# main.net
KiCad netlist of a schematic drawn in EAGLE
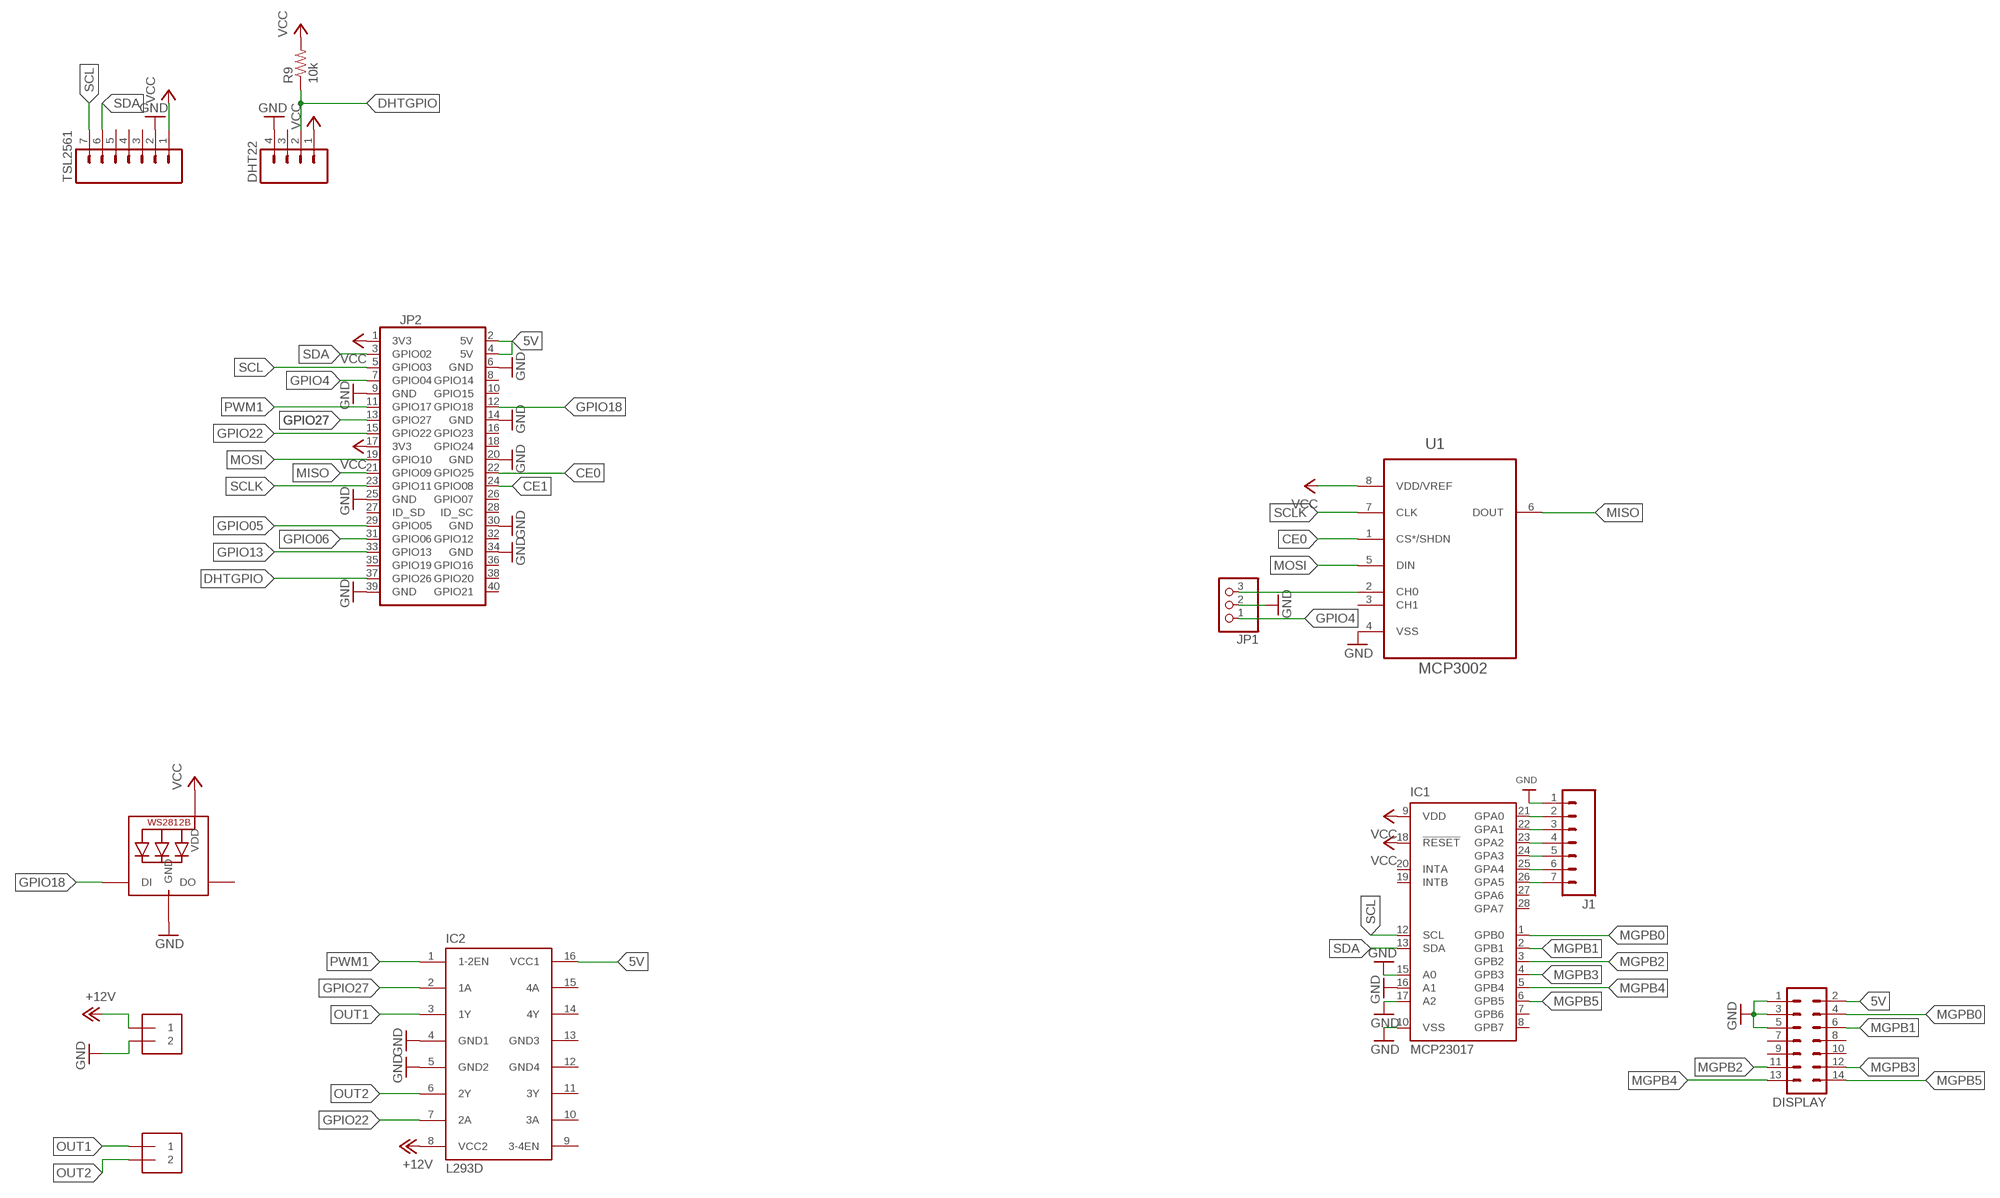
[diagram p0: schematic, sheet 1]

(export (version "E")
  (design (tool "Eeschema 10.0.6"))
  (components
    (comp (ref "DHT22")
      (value "M041X04_NO_SILK")
      (footprint "eagle-import:1X04_NO_SILK")
      (libsource (lib "eagle-import") (part "M041X04_NO_SILK"))
    )
    (comp (ref "DISPLAY")
      (value "MA07-2")
      (footprint "eagle-import:MA07-2")
      (libsource (lib "eagle-import") (part "MA07-2"))
    )
    (comp (ref "IC1")
      (value "MCP23017")
      (footprint "eagle-import:DIL28-3-ROUND")
      (libsource (lib "eagle-import") (part "MCP23017SP2"))
    )
    (comp (ref "IC2")
      (value "L293D")
      (footprint "eagle-import:DIL16")
      (libsource (lib "eagle-import") (part "L293D"))
    )
    (comp (ref "J1")
      (value "M07")
      (footprint "eagle-import:1X07")
      (libsource (lib "eagle-import") (part "M07"))
    )
    (comp (ref "J2")
      (value "1X2-3.5MM")
      (footprint "eagle-import:1X2-3.5MM")
      (libsource (lib "eagle-import") (part "1X2-3.5MM"))
    )
    (comp (ref "J3")
      (value "1X2-3.5MM")
      (footprint "eagle-import:1X2-3.5MM")
      (libsource (lib "eagle-import") (part "1X2-3.5MM"))
    )
    (comp (ref "JP1")
      (value "PINHD-1X3")
      (footprint "eagle-import:1X03")
      (libsource (lib "eagle-import") (part "PINHD-1X3"))
    )
    (comp (ref "JP2")
      (value "40W_PI_HAT_TPH")
      (footprint "eagle-import:2X20")
      (libsource (lib "eagle-import") (part "40W_PI_HAT_TPH"))
    )
    (comp (ref "LED2")
      (value "WS2812BTH")
      (footprint "eagle-import:LED5MMRGB")
      (libsource (lib "eagle-import") (part "WS2812BTH"))
    )
    (comp (ref "R9")
      (value "10k")
      (footprint "eagle-import:0204_7")
      (libsource (lib "eagle-import") (part "R-US_0204/7"))
    )
    (comp (ref "TSL2561")
      (value "M07NO_SILK")
      (footprint "eagle-import:1X07_NO_SILK")
      (libsource (lib "eagle-import") (part "M07NO_SILK"))
    )
    (comp (ref "U1")
      (value "MCP3002")
      (footprint "eagle-import:DIP254P762X533-8")
      (fields (field (name "MPN") "MCP3002-I/P"))
      (libsource (lib "eagle-import") (part "MCP3002-I/P"))
    )
  )
  (nets
    (net (code "1") (name "+12V") (class "Default")
      (node (ref "IC2") (pin "8") (pinfunction "VCC2_8") (pintype "power_in"))
      (node (ref "J2") (pin "1") (pinfunction "1_1") (pintype "passive"))
    )
    (net (code "2") (name "/GND3") (class "Default")
      (node (ref "IC2") (pin "13") (pinfunction "GND3_13") (pintype "power_in"))
    )
    (net (code "3") (name "/GND4") (class "Default")
      (node (ref "IC2") (pin "12") (pinfunction "GND4_12") (pintype "power_in"))
    )
    (net (code "4") (name "5V") (class "Default")
      (node (ref "DISPLAY") (pin "2") (pinfunction "2_2") (pintype "passive"))
      (node (ref "IC2") (pin "16") (pinfunction "VCC1_16") (pintype "power_in"))
      (node (ref "JP2") (pin "2") (pinfunction "5V_2") (pintype "passive"))
      (node (ref "JP2") (pin "4") (pinfunction "5V_4") (pintype "passive"))
    )
    (net (code "5") (name "CE0") (class "Default")
      (node (ref "JP2") (pin "22") (pinfunction "GPIO25_22") (pintype "passive"))
      (node (ref "U1") (pin "1") (pinfunction "CS*/SHDN_1") (pintype "input"))
    )
    (net (code "6") (name "CE1") (class "Default")
      (node (ref "JP2") (pin "24") (pinfunction "GPIO08_24") (pintype "passive"))
    )
    (net (code "7") (name "DHTGPIO") (class "Default")
      (node (ref "DHT22") (pin "2") (pinfunction "2_2") (pintype "passive"))
      (node (ref "JP2") (pin "37") (pinfunction "GPIO26_37") (pintype "passive"))
      (node (ref "R9") (pin "1") (pinfunction "1_1") (pintype "passive"))
    )
    (net (code "8") (name "GND") (class "Default")
      (node (ref "DHT22") (pin "4") (pinfunction "4_4") (pintype "passive"))
      (node (ref "DISPLAY") (pin "1") (pinfunction "1_1") (pintype "passive"))
      (node (ref "DISPLAY") (pin "3") (pinfunction "3_3") (pintype "passive"))
      (node (ref "DISPLAY") (pin "5") (pinfunction "5_5") (pintype "passive"))
      (node (ref "IC1") (pin "10") (pinfunction "VSS_10") (pintype "power_in"))
      (node (ref "IC1") (pin "15") (pinfunction "A0_15") (pintype "input"))
      (node (ref "IC1") (pin "16") (pinfunction "A1_16") (pintype "input"))
      (node (ref "IC1") (pin "17") (pinfunction "A2_17") (pintype "input"))
      (node (ref "IC2") (pin "4") (pinfunction "GND1_4") (pintype "power_in"))
      (node (ref "IC2") (pin "5") (pinfunction "GND2_5") (pintype "power_in"))
      (node (ref "J1") (pin "1") (pinfunction "1_1") (pintype "passive"))
      (node (ref "J2") (pin "2") (pinfunction "2_2") (pintype "passive"))
      (node (ref "JP1") (pin "2") (pinfunction "2_2") (pintype "passive"))
      (node (ref "JP2") (pin "14") (pinfunction "GND_14") (pintype "passive"))
      (node (ref "JP2") (pin "20") (pinfunction "GND_20") (pintype "passive"))
      (node (ref "JP2") (pin "25") (pinfunction "GND_25") (pintype "passive"))
      (node (ref "JP2") (pin "30") (pinfunction "GND_30") (pintype "passive"))
      (node (ref "JP2") (pin "34") (pinfunction "GND_34") (pintype "passive"))
      (node (ref "JP2") (pin "39") (pinfunction "GND_39") (pintype "passive"))
      (node (ref "JP2") (pin "6") (pinfunction "GND_6") (pintype "passive"))
      (node (ref "JP2") (pin "9") (pinfunction "GND_9") (pintype "passive"))
      (node (ref "LED2") (pin "2") (pinfunction "GND_2") (pintype "power_in"))
      (node (ref "TSL2561") (pin "2") (pinfunction "2_2") (pintype "passive"))
      (node (ref "U1") (pin "4") (pinfunction "VSS_4") (pintype "passive"))
    )
    (net (code "9") (name "GPIO4") (class "Default")
      (node (ref "JP1") (pin "1") (pinfunction "1_1") (pintype "passive"))
      (node (ref "JP2") (pin "7") (pinfunction "GPIO04_7") (pintype "passive"))
    )
    (net (code "10") (name "GPIO05") (class "Default")
      (node (ref "JP2") (pin "29") (pinfunction "GPIO05_29") (pintype "passive"))
    )
    (net (code "11") (name "GPIO06") (class "Default")
      (node (ref "JP2") (pin "31") (pinfunction "GPIO06_31") (pintype "passive"))
    )
    (net (code "12") (name "GPIO13") (class "Default")
      (node (ref "JP2") (pin "33") (pinfunction "GPIO13_33") (pintype "passive"))
    )
    (net (code "13") (name "GPIO18") (class "Default")
      (node (ref "JP2") (pin "12") (pinfunction "GPIO18_12") (pintype "passive"))
      (node (ref "LED2") (pin "4") (pinfunction "DI_4") (pintype "input"))
    )
    (net (code "14") (name "GPIO22") (class "Default")
      (node (ref "IC2") (pin "7") (pinfunction "2A_7") (pintype "input"))
      (node (ref "JP2") (pin "15") (pinfunction "GPIO22_15") (pintype "passive"))
    )
    (net (code "15") (name "GPIO27") (class "Default")
      (node (ref "IC2") (pin "2") (pinfunction "1A_2") (pintype "input"))
      (node (ref "JP2") (pin "13") (pinfunction "GPIO27_13") (pintype "passive"))
    )
    (net (code "16") (name "MGPB0") (class "Default")
      (node (ref "DISPLAY") (pin "4") (pinfunction "4_4") (pintype "passive"))
      (node (ref "IC1") (pin "1") (pinfunction "GPB0_1") (pintype "bidirectional"))
    )
    (net (code "17") (name "MGPB1") (class "Default")
      (node (ref "DISPLAY") (pin "6") (pinfunction "6_6") (pintype "passive"))
      (node (ref "IC1") (pin "2") (pinfunction "GPB1_2") (pintype "bidirectional"))
    )
    (net (code "18") (name "MGPB2") (class "Default")
      (node (ref "DISPLAY") (pin "11") (pinfunction "11_11") (pintype "passive"))
      (node (ref "IC1") (pin "3") (pinfunction "GPB2_3") (pintype "bidirectional"))
    )
    (net (code "19") (name "MGPB3") (class "Default")
      (node (ref "DISPLAY") (pin "12") (pinfunction "12_12") (pintype "passive"))
      (node (ref "IC1") (pin "4") (pinfunction "GPB3_4") (pintype "bidirectional"))
    )
    (net (code "20") (name "MGPB4") (class "Default")
      (node (ref "DISPLAY") (pin "13") (pinfunction "13_13") (pintype "passive"))
      (node (ref "IC1") (pin "5") (pinfunction "GPB4_5") (pintype "bidirectional"))
    )
    (net (code "21") (name "MGPB5") (class "Default")
      (node (ref "DISPLAY") (pin "14") (pinfunction "14_14") (pintype "passive"))
      (node (ref "IC1") (pin "6") (pinfunction "GPB5_6") (pintype "bidirectional"))
    )
    (net (code "22") (name "MISO") (class "Default")
      (node (ref "JP2") (pin "21") (pinfunction "GPIO09_21") (pintype "passive"))
      (node (ref "U1") (pin "6") (pinfunction "DOUT_6") (pintype "output"))
    )
    (net (code "23") (name "MOSI") (class "Default")
      (node (ref "JP2") (pin "19") (pinfunction "GPIO10_19") (pintype "passive"))
      (node (ref "U1") (pin "5") (pinfunction "DIN_5") (pintype "input"))
    )
    (net (code "24") (name "Net-(IC1-GPA0)") (class "Default")
      (node (ref "IC1") (pin "21") (pinfunction "GPA0_21") (pintype "bidirectional"))
      (node (ref "J1") (pin "2") (pinfunction "2_2") (pintype "passive"))
    )
    (net (code "25") (name "Net-(IC1-GPA1)") (class "Default")
      (node (ref "IC1") (pin "22") (pinfunction "GPA1_22") (pintype "bidirectional"))
      (node (ref "J1") (pin "3") (pinfunction "3_3") (pintype "passive"))
    )
    (net (code "26") (name "Net-(IC1-GPA2)") (class "Default")
      (node (ref "IC1") (pin "23") (pinfunction "GPA2_23") (pintype "bidirectional"))
      (node (ref "J1") (pin "4") (pinfunction "4_4") (pintype "passive"))
    )
    (net (code "27") (name "Net-(IC1-GPA3)") (class "Default")
      (node (ref "IC1") (pin "24") (pinfunction "GPA3_24") (pintype "bidirectional"))
      (node (ref "J1") (pin "5") (pinfunction "5_5") (pintype "passive"))
    )
    (net (code "28") (name "Net-(IC1-GPA4)") (class "Default")
      (node (ref "IC1") (pin "25") (pinfunction "GPA4_25") (pintype "bidirectional"))
      (node (ref "J1") (pin "6") (pinfunction "6_6") (pintype "passive"))
    )
    (net (code "29") (name "Net-(IC1-GPA5)") (class "Default")
      (node (ref "IC1") (pin "26") (pinfunction "GPA5_26") (pintype "bidirectional"))
      (node (ref "J1") (pin "7") (pinfunction "7_7") (pintype "passive"))
    )
    (net (code "30") (name "Net-(U1-CH0)") (class "Default")
      (node (ref "JP1") (pin "3") (pinfunction "3_3") (pintype "passive"))
      (node (ref "U1") (pin "2") (pinfunction "CH0_2") (pintype "input"))
    )
    (net (code "31") (name "OUT1") (class "Default")
      (node (ref "IC2") (pin "3") (pinfunction "1Y_3") (pintype "output"))
      (node (ref "J3") (pin "1") (pinfunction "1_1") (pintype "passive"))
    )
    (net (code "32") (name "OUT2") (class "Default")
      (node (ref "IC2") (pin "6") (pinfunction "2Y_6") (pintype "output"))
      (node (ref "J3") (pin "2") (pinfunction "2_2") (pintype "passive"))
    )
    (net (code "33") (name "PWM1") (class "Default")
      (node (ref "IC2") (pin "1") (pinfunction "1-2EN_1") (pintype "input"))
      (node (ref "JP2") (pin "11") (pinfunction "GPIO17_11") (pintype "passive"))
    )
    (net (code "34") (name "SCL") (class "Default")
      (node (ref "IC1") (pin "12") (pinfunction "SCL_12") (pintype "input"))
      (node (ref "JP2") (pin "5") (pinfunction "GPIO03_5") (pintype "passive"))
      (node (ref "TSL2561") (pin "7") (pinfunction "7_7") (pintype "passive"))
    )
    (net (code "35") (name "SCLK") (class "Default")
      (node (ref "JP2") (pin "23") (pinfunction "GPIO11_23") (pintype "passive"))
      (node (ref "U1") (pin "7") (pinfunction "CLK_7") (pintype "input"))
    )
    (net (code "36") (name "SDA") (class "Default")
      (node (ref "IC1") (pin "13") (pinfunction "SDA_13") (pintype "bidirectional"))
      (node (ref "JP2") (pin "3") (pinfunction "GPIO02_3") (pintype "passive"))
      (node (ref "TSL2561") (pin "6") (pinfunction "6_6") (pintype "passive"))
    )
    (net (code "37") (name "VCC") (class "Default")
      (node (ref "DHT22") (pin "1") (pinfunction "1_1") (pintype "passive"))
      (node (ref "IC1") (pin "18") (pinfunction "~{RESET}_18") (pintype "input"))
      (node (ref "IC1") (pin "9") (pinfunction "VDD_9") (pintype "power_in"))
      (node (ref "JP2") (pin "1") (pinfunction "3V3_1") (pintype "passive"))
      (node (ref "JP2") (pin "17") (pinfunction "3V3_17") (pintype "passive"))
      (node (ref "LED2") (pin "3") (pinfunction "VDD_3") (pintype "power_in"))
      (node (ref "R9") (pin "2") (pinfunction "2_2") (pintype "passive"))
      (node (ref "TSL2561") (pin "1") (pinfunction "1_1") (pintype "passive"))
      (node (ref "U1") (pin "8") (pinfunction "VDD/VREF_8") (pintype "power_in"))
    )
    (net (code "38") (name "unconnected-(DHT22-Pad3)") (class "Default")
      (node (ref "DHT22") (pin "3") (pinfunction "3_3") (pintype "passive"))
    )
    (net (code "39") (name "unconnected-(DISPLAY-Pad7)") (class "Default")
      (node (ref "DISPLAY") (pin "7") (pinfunction "7_7") (pintype "passive"))
    )
    (net (code "40") (name "unconnected-(DISPLAY-Pad8)") (class "Default")
      (node (ref "DISPLAY") (pin "8") (pinfunction "8_8") (pintype "passive"))
    )
    (net (code "41") (name "unconnected-(DISPLAY-Pad9)") (class "Default")
      (node (ref "DISPLAY") (pin "9") (pinfunction "9_9") (pintype "passive"))
    )
    (net (code "42") (name "unconnected-(DISPLAY-Pad10)") (class "Default")
      (node (ref "DISPLAY") (pin "10") (pinfunction "10_10") (pintype "passive"))
    )
    (net (code "43") (name "unconnected-(IC1-GPA6-Pad27)") (class "Default")
      (node (ref "IC1") (pin "27") (pinfunction "GPA6_27") (pintype "bidirectional"))
    )
    (net (code "44") (name "unconnected-(IC1-GPA7-Pad28)") (class "Default")
      (node (ref "IC1") (pin "28") (pinfunction "GPA7_28") (pintype "bidirectional"))
    )
    (net (code "45") (name "unconnected-(IC1-GPB6-Pad7)") (class "Default")
      (node (ref "IC1") (pin "7") (pinfunction "GPB6_7") (pintype "bidirectional"))
    )
    (net (code "46") (name "unconnected-(IC1-GPB7-Pad8)") (class "Default")
      (node (ref "IC1") (pin "8") (pinfunction "GPB7_8") (pintype "bidirectional"))
    )
    (net (code "47") (name "unconnected-(IC1-INTA-Pad20)") (class "Default")
      (node (ref "IC1") (pin "20") (pinfunction "INTA_20") (pintype "output"))
    )
    (net (code "48") (name "unconnected-(IC1-INTB-Pad19)") (class "Default")
      (node (ref "IC1") (pin "19") (pinfunction "INTB_19") (pintype "output"))
    )
    (net (code "49") (name "unconnected-(IC2-3-4EN-Pad9)") (class "Default")
      (node (ref "IC2") (pin "9") (pinfunction "3-4EN_9") (pintype "input"))
    )
    (net (code "50") (name "unconnected-(IC2-3A-Pad10)") (class "Default")
      (node (ref "IC2") (pin "10") (pinfunction "3A_10") (pintype "input"))
    )
    (net (code "51") (name "unconnected-(IC2-3Y-Pad11)") (class "Default")
      (node (ref "IC2") (pin "11") (pinfunction "3Y_11") (pintype "output"))
    )
    (net (code "52") (name "unconnected-(IC2-4A-Pad15)") (class "Default")
      (node (ref "IC2") (pin "15") (pinfunction "4A_15") (pintype "input"))
    )
    (net (code "53") (name "unconnected-(IC2-4Y-Pad14)") (class "Default")
      (node (ref "IC2") (pin "14") (pinfunction "4Y_14") (pintype "output"))
    )
    (net (code "54") (name "unconnected-(JP2-GPIO07-Pad26)") (class "Default")
      (node (ref "JP2") (pin "26") (pinfunction "GPIO07_26") (pintype "passive"))
    )
    (net (code "55") (name "unconnected-(JP2-GPIO12-Pad32)") (class "Default")
      (node (ref "JP2") (pin "32") (pinfunction "GPIO12_32") (pintype "passive"))
    )
    (net (code "56") (name "unconnected-(JP2-GPIO14-Pad8)") (class "Default")
      (node (ref "JP2") (pin "8") (pinfunction "GPIO14_8") (pintype "passive"))
    )
    (net (code "57") (name "unconnected-(JP2-GPIO15-Pad10)") (class "Default")
      (node (ref "JP2") (pin "10") (pinfunction "GPIO15_10") (pintype "passive"))
    )
    (net (code "58") (name "unconnected-(JP2-GPIO16-Pad36)") (class "Default")
      (node (ref "JP2") (pin "36") (pinfunction "GPIO16_36") (pintype "passive"))
    )
    (net (code "59") (name "unconnected-(JP2-GPIO19-Pad35)") (class "Default")
      (node (ref "JP2") (pin "35") (pinfunction "GPIO19_35") (pintype "passive"))
    )
    (net (code "60") (name "unconnected-(JP2-GPIO20-Pad38)") (class "Default")
      (node (ref "JP2") (pin "38") (pinfunction "GPIO20_38") (pintype "passive"))
    )
    (net (code "61") (name "unconnected-(JP2-GPIO21-Pad40)") (class "Default")
      (node (ref "JP2") (pin "40") (pinfunction "GPIO21_40") (pintype "passive"))
    )
    (net (code "62") (name "unconnected-(JP2-GPIO23-Pad16)") (class "Default")
      (node (ref "JP2") (pin "16") (pinfunction "GPIO23_16") (pintype "passive"))
    )
    (net (code "63") (name "unconnected-(JP2-GPIO24-Pad18)") (class "Default")
      (node (ref "JP2") (pin "18") (pinfunction "GPIO24_18") (pintype "passive"))
    )
    (net (code "64") (name "unconnected-(JP2-ID_SC-Pad28)") (class "Default")
      (node (ref "JP2") (pin "28") (pinfunction "ID_SC_28") (pintype "passive"))
    )
    (net (code "65") (name "unconnected-(JP2-ID_SD-Pad27)") (class "Default")
      (node (ref "JP2") (pin "27") (pinfunction "ID_SD_27") (pintype "passive"))
    )
    (net (code "66") (name "unconnected-(LED2-DO-Pad1)") (class "Default")
      (node (ref "LED2") (pin "1") (pinfunction "DO_1") (pintype "output"))
    )
    (net (code "67") (name "unconnected-(TSL2561-Pad3)") (class "Default")
      (node (ref "TSL2561") (pin "3") (pinfunction "3_3") (pintype "passive"))
    )
    (net (code "68") (name "unconnected-(TSL2561-Pad4)") (class "Default")
      (node (ref "TSL2561") (pin "4") (pinfunction "4_4") (pintype "passive"))
    )
    (net (code "69") (name "unconnected-(TSL2561-Pad5)") (class "Default")
      (node (ref "TSL2561") (pin "5") (pinfunction "5_5") (pintype "passive"))
    )
    (net (code "70") (name "unconnected-(U1-CH1-Pad3)") (class "Default")
      (node (ref "U1") (pin "3") (pinfunction "CH1_3") (pintype "input"))
    )
  )
)
